# Sheet1.net
KiCad netlist of a schematic drawn in Altium Designer
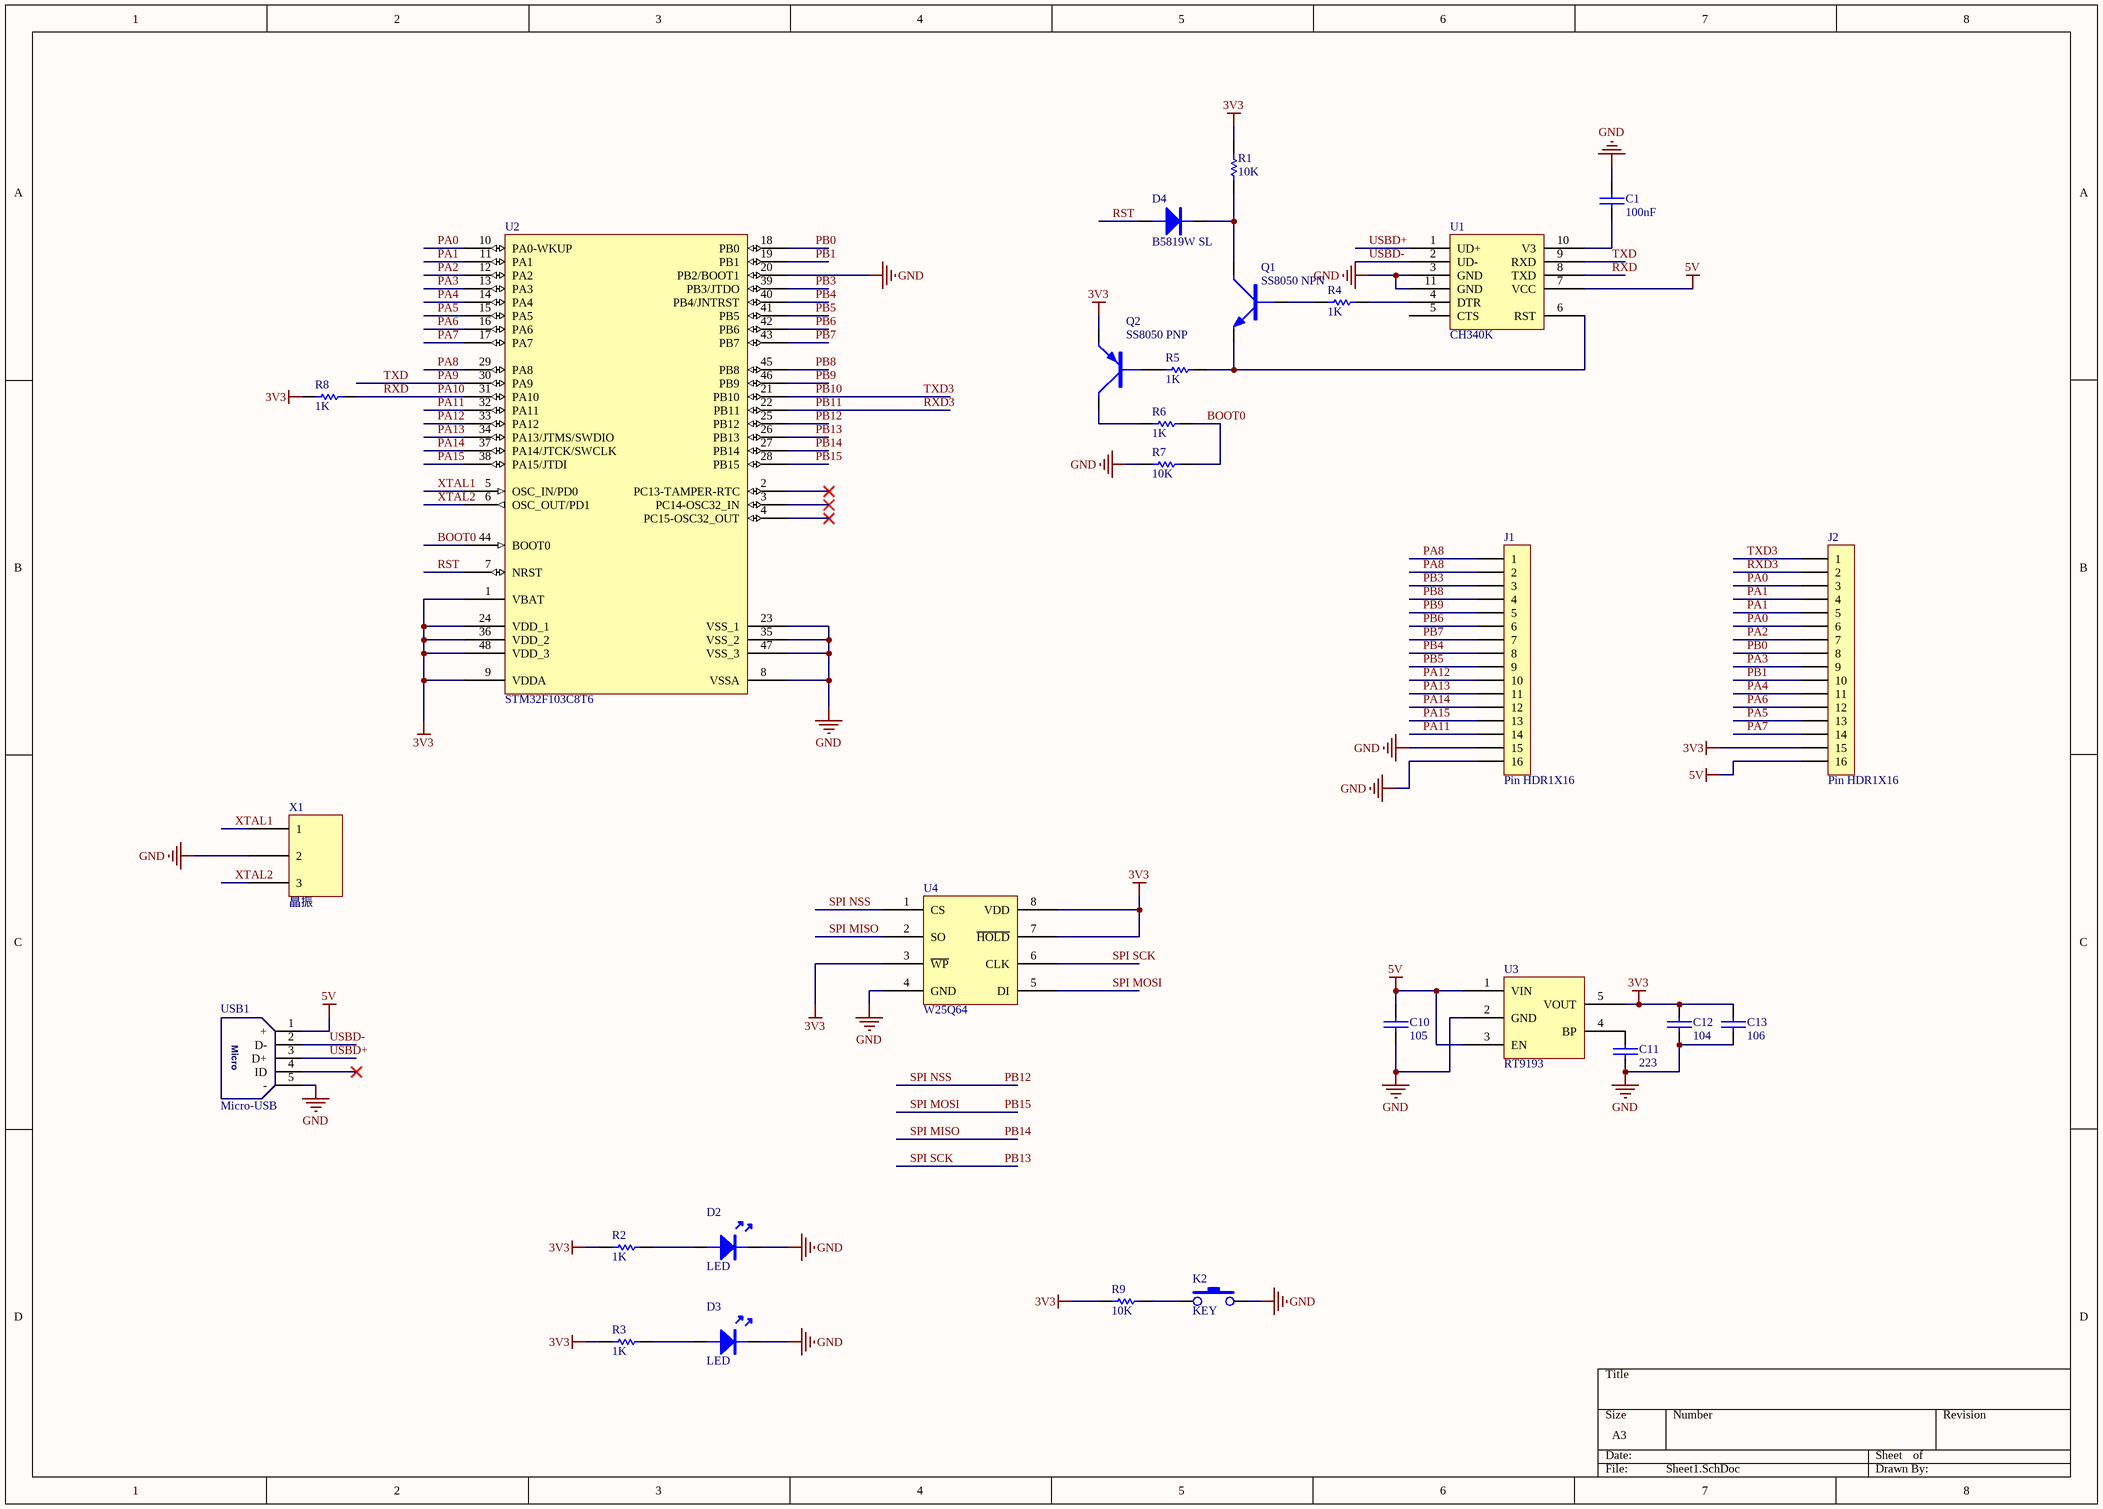
[diagram p0: Sheet1.SchDoc]

(export (version "E")
  (design (tool "Eeschema 10.0.6"))
  (components
    (comp (ref "C1")
      (value "100nF")
      (footprint "0603C")
      (description "无极性电容")
      (libsource (lib "电容") (part "CAP"))
    )
    (comp (ref "C10")
      (value "105")
      (footprint "0603C")
      (description "无极性电容")
      (libsource (lib "电容") (part "CAP"))
    )
    (comp (ref "C11")
      (value "223")
      (footprint "0603C")
      (description "无极性电容")
      (libsource (lib "电容") (part "CAP"))
    )
    (comp (ref "C12")
      (value "104")
      (footprint "0603C")
      (description "无极性电容")
      (libsource (lib "电容") (part "CAP"))
    )
    (comp (ref "C13")
      (value "106")
      (footprint "0603C")
      (description "无极性电容")
      (libsource (lib "电容") (part "CAP"))
    )
    (comp (ref "D2") (value "LED") (footprint "LED-0603G") (libsource (lib "LED") (part "LED")))
    (comp (ref "D3") (value "LED") (footprint "LED-0603G") (libsource (lib "LED") (part "LED")))
    (comp (ref "D4")
      (value "B5819W SL")
      (footprint "SOD-123")
      (description "普通二极管")
      (libsource (lib "二极管") (part "DIODE"))
    )
    (comp (ref "J1")
      (value "Pin HDR1X16")
      (footprint "Pin HDR1X16/2.54mm-S")
      (libsource (lib "排针") (part "Pin HDR1X16"))
    )
    (comp (ref "J2")
      (value "Pin HDR1X16")
      (footprint "Pin HDR1X16/2.54mm-S")
      (libsource (lib "排针") (part "Pin HDR1X16"))
    )
    (comp (ref "K2") (value "KEY") (footprint "SMD-3X6X2.5") (libsource (lib "轻触开关") (part "KEY")))
    (comp (ref "Q1")
      (value "SS8050 NPN")
      (footprint "SOT-23")
      (description "NPN三极管")
      (libsource (lib "三极管") (part "NPN"))
    )
    (comp (ref "Q2")
      (value "SS8050 PNP")
      (footprint "SOT-23")
      (description "PNP三极管")
      (libsource (lib "三极管") (part "PNP"))
    )
    (comp (ref "R1") (value "10K") (footprint "0603R") (libsource (lib "电阻") (part "RES")))
    (comp (ref "R2") (value "1K") (footprint "0603R") (libsource (lib "电阻") (part "RES")))
    (comp (ref "R3") (value "1K") (footprint "0603R") (libsource (lib "电阻") (part "RES")))
    (comp (ref "R4") (value "1K") (footprint "0603R") (libsource (lib "电阻") (part "RES")))
    (comp (ref "R5") (value "1K") (footprint "0603R") (libsource (lib "电阻") (part "RES")))
    (comp (ref "R6") (value "1K") (footprint "0603R") (libsource (lib "电阻") (part "RES")))
    (comp (ref "R7") (value "10K") (footprint "0603R") (libsource (lib "电阻") (part "RES")))
    (comp (ref "R8") (value "1K") (footprint "0603R") (libsource (lib "电阻") (part "RES")))
    (comp (ref "R9") (value "10K") (footprint "0603R") (libsource (lib "电阻") (part "RES")))
    (comp (ref "U1") (value "CH340K") (footprint "ESSOP-10") (libsource (lib "Schlib1") (part "CH340K")))
    (comp (ref "U2")
      (value "STM32F103C8T6")
      (footprint "LQFP48 7X7")
      (libsource (lib "STM32系列") (part "STM32F103C8T6"))
    )
    (comp (ref "U3") (value "RT9193") (footprint "RT9193-33GB") (libsource (lib "Schlib1") (part "RT9193")))
    (comp (ref "U4") (value "W25Q64") (footprint "SOIC-8") (libsource (lib "Schlib1") (part "W25Q64")))
    (comp (ref "USB1")
      (value "Micro-USB")
      (footprint "USB-micro_B")
      (libsource (lib "USB") (part "Micro-USB"))
    )
    (comp (ref "X1") (value "晶振") (footprint "8MHZ") (libsource (lib "Schlib1") (part "8MHZ")))
  )
  (nets
    (net (code "1") (name "/BOOT0") (class "Default")
      (node (ref "R6") (pin "2") (pinfunction "2_2") (pintype "passive"))
      (node (ref "R7") (pin "1") (pinfunction "1_1") (pintype "passive"))
      (node (ref "U2") (pin "44") (pinfunction "BOOT0_44") (pintype "input"))
    )
    (net (code "2") (name "/PA0") (class "Default")
      (node (ref "J2") (pin "3") (pinfunction "3_3") (pintype "passive"))
      (node (ref "J2") (pin "6") (pinfunction "6_6") (pintype "passive"))
      (node (ref "U2") (pin "10") (pinfunction "PA0-WKUP_10") (pintype "bidirectional"))
    )
    (net (code "3") (name "/PA1") (class "Default")
      (node (ref "J2") (pin "4") (pinfunction "4_4") (pintype "passive"))
      (node (ref "J2") (pin "5") (pinfunction "5_5") (pintype "passive"))
      (node (ref "U2") (pin "11") (pinfunction "PA1_11") (pintype "bidirectional"))
    )
    (net (code "4") (name "/PA2") (class "Default")
      (node (ref "J2") (pin "7") (pinfunction "7_7") (pintype "passive"))
      (node (ref "U2") (pin "12") (pinfunction "PA2_12") (pintype "bidirectional"))
    )
    (net (code "5") (name "/PA3") (class "Default")
      (node (ref "J2") (pin "9") (pinfunction "9_9") (pintype "passive"))
      (node (ref "U2") (pin "13") (pinfunction "PA3_13") (pintype "bidirectional"))
    )
    (net (code "6") (name "/PA4") (class "Default")
      (node (ref "J2") (pin "11") (pinfunction "11_11") (pintype "passive"))
      (node (ref "U2") (pin "14") (pinfunction "PA4_14") (pintype "bidirectional"))
    )
    (net (code "7") (name "/PA5") (class "Default")
      (node (ref "J2") (pin "13") (pinfunction "13_13") (pintype "passive"))
      (node (ref "U2") (pin "15") (pinfunction "PA5_15") (pintype "bidirectional"))
    )
    (net (code "8") (name "/PA6") (class "Default")
      (node (ref "J2") (pin "12") (pinfunction "12_12") (pintype "passive"))
      (node (ref "U2") (pin "16") (pinfunction "PA6_16") (pintype "bidirectional"))
    )
    (net (code "9") (name "/PA7") (class "Default")
      (node (ref "J2") (pin "14") (pinfunction "14_14") (pintype "passive"))
      (node (ref "U2") (pin "17") (pinfunction "PA7_17") (pintype "bidirectional"))
    )
    (net (code "10") (name "/PA8") (class "Default")
      (node (ref "J1") (pin "1") (pinfunction "1_1") (pintype "passive"))
      (node (ref "J1") (pin "2") (pinfunction "2_2") (pintype "passive"))
      (node (ref "U2") (pin "29") (pinfunction "PA8_29") (pintype "bidirectional"))
    )
    (net (code "11") (name "/PA9") (class "Default")
      (node (ref "U1") (pin "9") (pinfunction "RXD_9") (pintype "passive"))
      (node (ref "U2") (pin "30") (pinfunction "PA9_30") (pintype "bidirectional"))
    )
    (net (code "12") (name "/PA10") (class "Default")
      (node (ref "R8") (pin "2") (pinfunction "2_2") (pintype "passive"))
      (node (ref "U1") (pin "8") (pinfunction "TXD_8") (pintype "passive"))
      (node (ref "U2") (pin "31") (pinfunction "PA10_31") (pintype "bidirectional"))
    )
    (net (code "13") (name "/PA11") (class "Default")
      (node (ref "J1") (pin "14") (pinfunction "14_14") (pintype "passive"))
      (node (ref "U2") (pin "32") (pinfunction "PA11_32") (pintype "bidirectional"))
    )
    (net (code "14") (name "/PA12") (class "Default")
      (node (ref "J1") (pin "10") (pinfunction "10_10") (pintype "passive"))
      (node (ref "U2") (pin "33") (pinfunction "PA12_33") (pintype "bidirectional"))
    )
    (net (code "15") (name "/PA13") (class "Default")
      (node (ref "J1") (pin "11") (pinfunction "11_11") (pintype "passive"))
      (node (ref "U2") (pin "34") (pinfunction "PA13/JTMS/SWDIO_34") (pintype "bidirectional"))
    )
    (net (code "16") (name "/PA14") (class "Default")
      (node (ref "J1") (pin "12") (pinfunction "12_12") (pintype "passive"))
      (node (ref "U2") (pin "37") (pinfunction "PA14/JTCK/SWCLK_37") (pintype "bidirectional"))
    )
    (net (code "17") (name "/PA15") (class "Default")
      (node (ref "J1") (pin "13") (pinfunction "13_13") (pintype "passive"))
      (node (ref "U2") (pin "38") (pinfunction "PA15/JTDI_38") (pintype "bidirectional"))
    )
    (net (code "18") (name "/PB0") (class "Default")
      (node (ref "J2") (pin "8") (pinfunction "8_8") (pintype "passive"))
      (node (ref "U2") (pin "18") (pinfunction "PB0_18") (pintype "bidirectional"))
    )
    (net (code "19") (name "/PB1") (class "Default")
      (node (ref "J2") (pin "10") (pinfunction "10_10") (pintype "passive"))
      (node (ref "U2") (pin "19") (pinfunction "PB1_19") (pintype "bidirectional"))
    )
    (net (code "20") (name "/PB3") (class "Default")
      (node (ref "J1") (pin "3") (pinfunction "3_3") (pintype "passive"))
      (node (ref "U2") (pin "39") (pinfunction "PB3/JTDO_39") (pintype "bidirectional"))
    )
    (net (code "21") (name "/PB4") (class "Default")
      (node (ref "J1") (pin "8") (pinfunction "8_8") (pintype "passive"))
      (node (ref "U2") (pin "40") (pinfunction "PB4/JNTRST_40") (pintype "bidirectional"))
    )
    (net (code "22") (name "/PB5") (class "Default")
      (node (ref "J1") (pin "9") (pinfunction "9_9") (pintype "passive"))
      (node (ref "U2") (pin "41") (pinfunction "PB5_41") (pintype "bidirectional"))
    )
    (net (code "23") (name "/PB6") (class "Default")
      (node (ref "J1") (pin "6") (pinfunction "6_6") (pintype "passive"))
      (node (ref "U2") (pin "42") (pinfunction "PB6_42") (pintype "bidirectional"))
    )
    (net (code "24") (name "/PB7") (class "Default")
      (node (ref "J1") (pin "7") (pinfunction "7_7") (pintype "passive"))
      (node (ref "U2") (pin "43") (pinfunction "PB7_43") (pintype "bidirectional"))
    )
    (net (code "25") (name "/PB8") (class "Default")
      (node (ref "J1") (pin "4") (pinfunction "4_4") (pintype "passive"))
      (node (ref "U2") (pin "45") (pinfunction "PB8_45") (pintype "bidirectional"))
    )
    (net (code "26") (name "/PB9") (class "Default")
      (node (ref "J1") (pin "5") (pinfunction "5_5") (pintype "passive"))
      (node (ref "U2") (pin "46") (pinfunction "PB9_46") (pintype "bidirectional"))
    )
    (net (code "27") (name "/PB10") (class "Default")
      (node (ref "J2") (pin "1") (pinfunction "1_1") (pintype "passive"))
      (node (ref "U2") (pin "21") (pinfunction "PB10_21") (pintype "bidirectional"))
    )
    (net (code "28") (name "/PB11") (class "Default")
      (node (ref "J2") (pin "2") (pinfunction "2_2") (pintype "passive"))
      (node (ref "U2") (pin "22") (pinfunction "PB11_22") (pintype "bidirectional"))
    )
    (net (code "29") (name "/PB12") (class "Default")
      (node (ref "U2") (pin "25") (pinfunction "PB12_25") (pintype "bidirectional"))
      (node (ref "U4") (pin "1") (pinfunction "CS_1") (pintype "passive"))
    )
    (net (code "30") (name "/PB13") (class "Default")
      (node (ref "U2") (pin "26") (pinfunction "PB13_26") (pintype "bidirectional"))
      (node (ref "U4") (pin "6") (pinfunction "CLK_6") (pintype "passive"))
    )
    (net (code "31") (name "/PB14") (class "Default")
      (node (ref "U2") (pin "27") (pinfunction "PB14_27") (pintype "bidirectional"))
      (node (ref "U4") (pin "2") (pinfunction "SO_2") (pintype "passive"))
    )
    (net (code "32") (name "/PB15") (class "Default")
      (node (ref "U2") (pin "28") (pinfunction "PB15_28") (pintype "bidirectional"))
      (node (ref "U4") (pin "5") (pinfunction "DI_5") (pintype "passive"))
    )
    (net (code "33") (name "/RST") (class "Default")
      (node (ref "D4") (pin "A") (pinfunction "A_A") (pintype "passive"))
      (node (ref "U2") (pin "7") (pinfunction "NRST_7") (pintype "bidirectional"))
    )
    (net (code "34") (name "/USBD+") (class "Default")
      (node (ref "U1") (pin "1") (pinfunction "UD+_1") (pintype "passive"))
      (node (ref "USB1") (pin "3") (pinfunction "D+_3") (pintype "passive"))
    )
    (net (code "35") (name "/USBD-") (class "Default")
      (node (ref "U1") (pin "2") (pinfunction "UD-_2") (pintype "passive"))
      (node (ref "USB1") (pin "2") (pinfunction "D-_2") (pintype "passive"))
    )
    (net (code "36") (name "/XTAL1") (class "Default")
      (node (ref "U2") (pin "5") (pinfunction "OSC_IN/PD0_5") (pintype "input"))
      (node (ref "X1") (pin "1") (pinfunction "1_1") (pintype "passive"))
    )
    (net (code "37") (name "/XTAL2") (class "Default")
      (node (ref "U2") (pin "6") (pinfunction "OSC_OUT/PD1_6") (pintype "output"))
      (node (ref "X1") (pin "3") (pinfunction "3_3") (pintype "passive"))
    )
    (net (code "38") (name "3V3") (class "Default")
      (node (ref "C12") (pin "2") (pinfunction "2_2") (pintype "passive"))
      (node (ref "C13") (pin "2") (pinfunction "2_2") (pintype "passive"))
      (node (ref "J2") (pin "15") (pinfunction "15_15") (pintype "passive"))
      (node (ref "Q2") (pin "E") (pinfunction "E_E") (pintype "passive"))
      (node (ref "R1") (pin "2") (pinfunction "2_2") (pintype "passive"))
      (node (ref "R2") (pin "1") (pinfunction "1_1") (pintype "passive"))
      (node (ref "R3") (pin "1") (pinfunction "1_1") (pintype "passive"))
      (node (ref "R8") (pin "1") (pinfunction "1_1") (pintype "passive"))
      (node (ref "R9") (pin "1") (pinfunction "1_1") (pintype "passive"))
      (node (ref "U2") (pin "1") (pinfunction "VBAT_1") (pintype "power_in"))
      (node (ref "U2") (pin "24") (pinfunction "VDD_1_24") (pintype "power_in"))
      (node (ref "U2") (pin "36") (pinfunction "VDD_2_36") (pintype "power_in"))
      (node (ref "U2") (pin "48") (pinfunction "VDD_3_48") (pintype "power_in"))
      (node (ref "U2") (pin "9") (pinfunction "VDDA_9") (pintype "power_in"))
      (node (ref "U3") (pin "5") (pinfunction "VOUT_5") (pintype "passive"))
      (node (ref "U4") (pin "3") (pinfunction "~{WP}_3") (pintype "passive"))
      (node (ref "U4") (pin "7") (pinfunction "~{HOLD}_7") (pintype "passive"))
      (node (ref "U4") (pin "8") (pinfunction "VDD_8") (pintype "passive"))
    )
    (net (code "39") (name "5V") (class "Default")
      (node (ref "C10") (pin "2") (pinfunction "2_2") (pintype "passive"))
      (node (ref "J2") (pin "16") (pinfunction "16_16") (pintype "passive"))
      (node (ref "U1") (pin "7") (pinfunction "VCC_7") (pintype "passive"))
      (node (ref "U3") (pin "1") (pinfunction "VIN_1") (pintype "passive"))
      (node (ref "U3") (pin "3") (pinfunction "EN_3") (pintype "passive"))
      (node (ref "USB1") (pin "1") (pinfunction "+_1") (pintype "passive"))
    )
    (net (code "40") (name "GND") (class "Default")
      (node (ref "C1") (pin "2") (pinfunction "2_2") (pintype "passive"))
      (node (ref "C10") (pin "1") (pinfunction "1_1") (pintype "passive"))
      (node (ref "C11") (pin "1") (pinfunction "1_1") (pintype "passive"))
      (node (ref "C12") (pin "1") (pinfunction "1_1") (pintype "passive"))
      (node (ref "C13") (pin "1") (pinfunction "1_1") (pintype "passive"))
      (node (ref "D2") (pin "K") (pinfunction "K_K") (pintype "passive"))
      (node (ref "D3") (pin "K") (pinfunction "K_K") (pintype "passive"))
      (node (ref "J1") (pin "15") (pinfunction "15_15") (pintype "passive"))
      (node (ref "J1") (pin "16") (pinfunction "16_16") (pintype "passive"))
      (node (ref "K2") (pin "3") (pinfunction "3_3") (pintype "passive"))
      (node (ref "R7") (pin "2") (pinfunction "2_2") (pintype "passive"))
      (node (ref "U1") (pin "11") (pinfunction "GND_11") (pintype "passive"))
      (node (ref "U1") (pin "3") (pinfunction "GND_3") (pintype "passive"))
      (node (ref "U2") (pin "20") (pinfunction "PB2/BOOT1_20") (pintype "bidirectional"))
      (node (ref "U2") (pin "23") (pinfunction "VSS_1_23") (pintype "passive"))
      (node (ref "U2") (pin "35") (pinfunction "VSS_2_35") (pintype "passive"))
      (node (ref "U2") (pin "47") (pinfunction "VSS_3_47") (pintype "passive"))
      (node (ref "U2") (pin "8") (pinfunction "VSSA_8") (pintype "passive"))
      (node (ref "U3") (pin "2") (pinfunction "GND_2") (pintype "passive"))
      (node (ref "U4") (pin "4") (pinfunction "GND_4") (pintype "passive"))
      (node (ref "USB1") (pin "5") (pinfunction "-_5") (pintype "passive"))
      (node (ref "X1") (pin "2") (pinfunction "2_2") (pintype "passive"))
    )
    (net (code "41") (name "Net-(D2-PadA)") (class "Default")
      (node (ref "D2") (pin "A") (pinfunction "A_A") (pintype "passive"))
      (node (ref "R2") (pin "2") (pinfunction "2_2") (pintype "passive"))
    )
    (net (code "42") (name "Net-(D3-PadA)") (class "Default")
      (node (ref "D3") (pin "A") (pinfunction "A_A") (pintype "passive"))
      (node (ref "R3") (pin "2") (pinfunction "2_2") (pintype "passive"))
    )
    (net (code "43") (name "Net-(D4-PadK)") (class "Default")
      (node (ref "D4") (pin "K") (pinfunction "K_K") (pintype "passive"))
      (node (ref "Q1") (pin "C") (pinfunction "C_C") (pintype "passive"))
      (node (ref "R1") (pin "1") (pinfunction "1_1") (pintype "passive"))
    )
    (net (code "44") (name "Net-(K2-Pad1)") (class "Default")
      (node (ref "K2") (pin "1") (pinfunction "1_1") (pintype "passive"))
      (node (ref "R9") (pin "2") (pinfunction "2_2") (pintype "passive"))
    )
    (net (code "45") (name "Net-(Q1-PadB)") (class "Default")
      (node (ref "Q1") (pin "B") (pinfunction "B_B") (pintype "passive"))
      (node (ref "R4") (pin "1") (pinfunction "1_1") (pintype "passive"))
    )
    (net (code "46") (name "Net-(Q2-PadB)") (class "Default")
      (node (ref "Q2") (pin "B") (pinfunction "B_B") (pintype "passive"))
      (node (ref "R5") (pin "1") (pinfunction "1_1") (pintype "passive"))
    )
    (net (code "47") (name "Net-(Q2-PadC)") (class "Default")
      (node (ref "Q2") (pin "C") (pinfunction "C_C") (pintype "passive"))
      (node (ref "R6") (pin "1") (pinfunction "1_1") (pintype "passive"))
    )
    (net (code "48") (name "Net-(U1-DTR)") (class "Default")
      (node (ref "R4") (pin "2") (pinfunction "2_2") (pintype "passive"))
      (node (ref "U1") (pin "4") (pinfunction "DTR_4") (pintype "passive"))
    )
    (net (code "49") (name "Net-(U1-RST)") (class "Default")
      (node (ref "Q1") (pin "E") (pinfunction "E_E") (pintype "passive"))
      (node (ref "R5") (pin "2") (pinfunction "2_2") (pintype "passive"))
      (node (ref "U1") (pin "6") (pinfunction "RST_6") (pintype "passive"))
    )
    (net (code "50") (name "Net-(U1-V3)") (class "Default")
      (node (ref "C1") (pin "1") (pinfunction "1_1") (pintype "passive"))
      (node (ref "U1") (pin "10") (pinfunction "V3_10") (pintype "passive"))
    )
    (net (code "51") (name "Net-(U3-BP)") (class "Default")
      (node (ref "C11") (pin "2") (pinfunction "2_2") (pintype "passive"))
      (node (ref "U3") (pin "4") (pinfunction "BP_4") (pintype "passive"))
    )
    (net (code "52") (name "unconnected-(U1-CTS-Pad5)") (class "Default")
      (node (ref "U1") (pin "5") (pinfunction "CTS_5") (pintype "passive"))
    )
    (net (code "53") (name "unconnected-(U2-PC13-TAMPER-RTC-Pad2)") (class "Default")
      (node (ref "U2") (pin "2") (pinfunction "PC13-TAMPER-RTC_2") (pintype "bidirectional+no_connect"))
    )
    (net (code "54") (name "unconnected-(U2-PC14-OSC32_IN-Pad3)") (class "Default")
      (node (ref "U2") (pin "3") (pinfunction "PC14-OSC32_IN_3") (pintype "bidirectional+no_connect"))
    )
    (net (code "55") (name "unconnected-(U2-PC15-OSC32_OUT-Pad4)") (class "Default")
      (node (ref "U2") (pin "4") (pinfunction "PC15-OSC32_OUT_4") (pintype "bidirectional+no_connect"))
    )
    (net (code "56") (name "unconnected-(USB1-ID-Pad4)") (class "Default")
      (node (ref "USB1") (pin "4") (pinfunction "ID_4") (pintype "passive+no_connect"))
    )
  )
)
